# PinscapePico_KL25Z_Adapter_-_74HC165_vsn.net
KiCad netlist of a schematic drawn in EAGLE
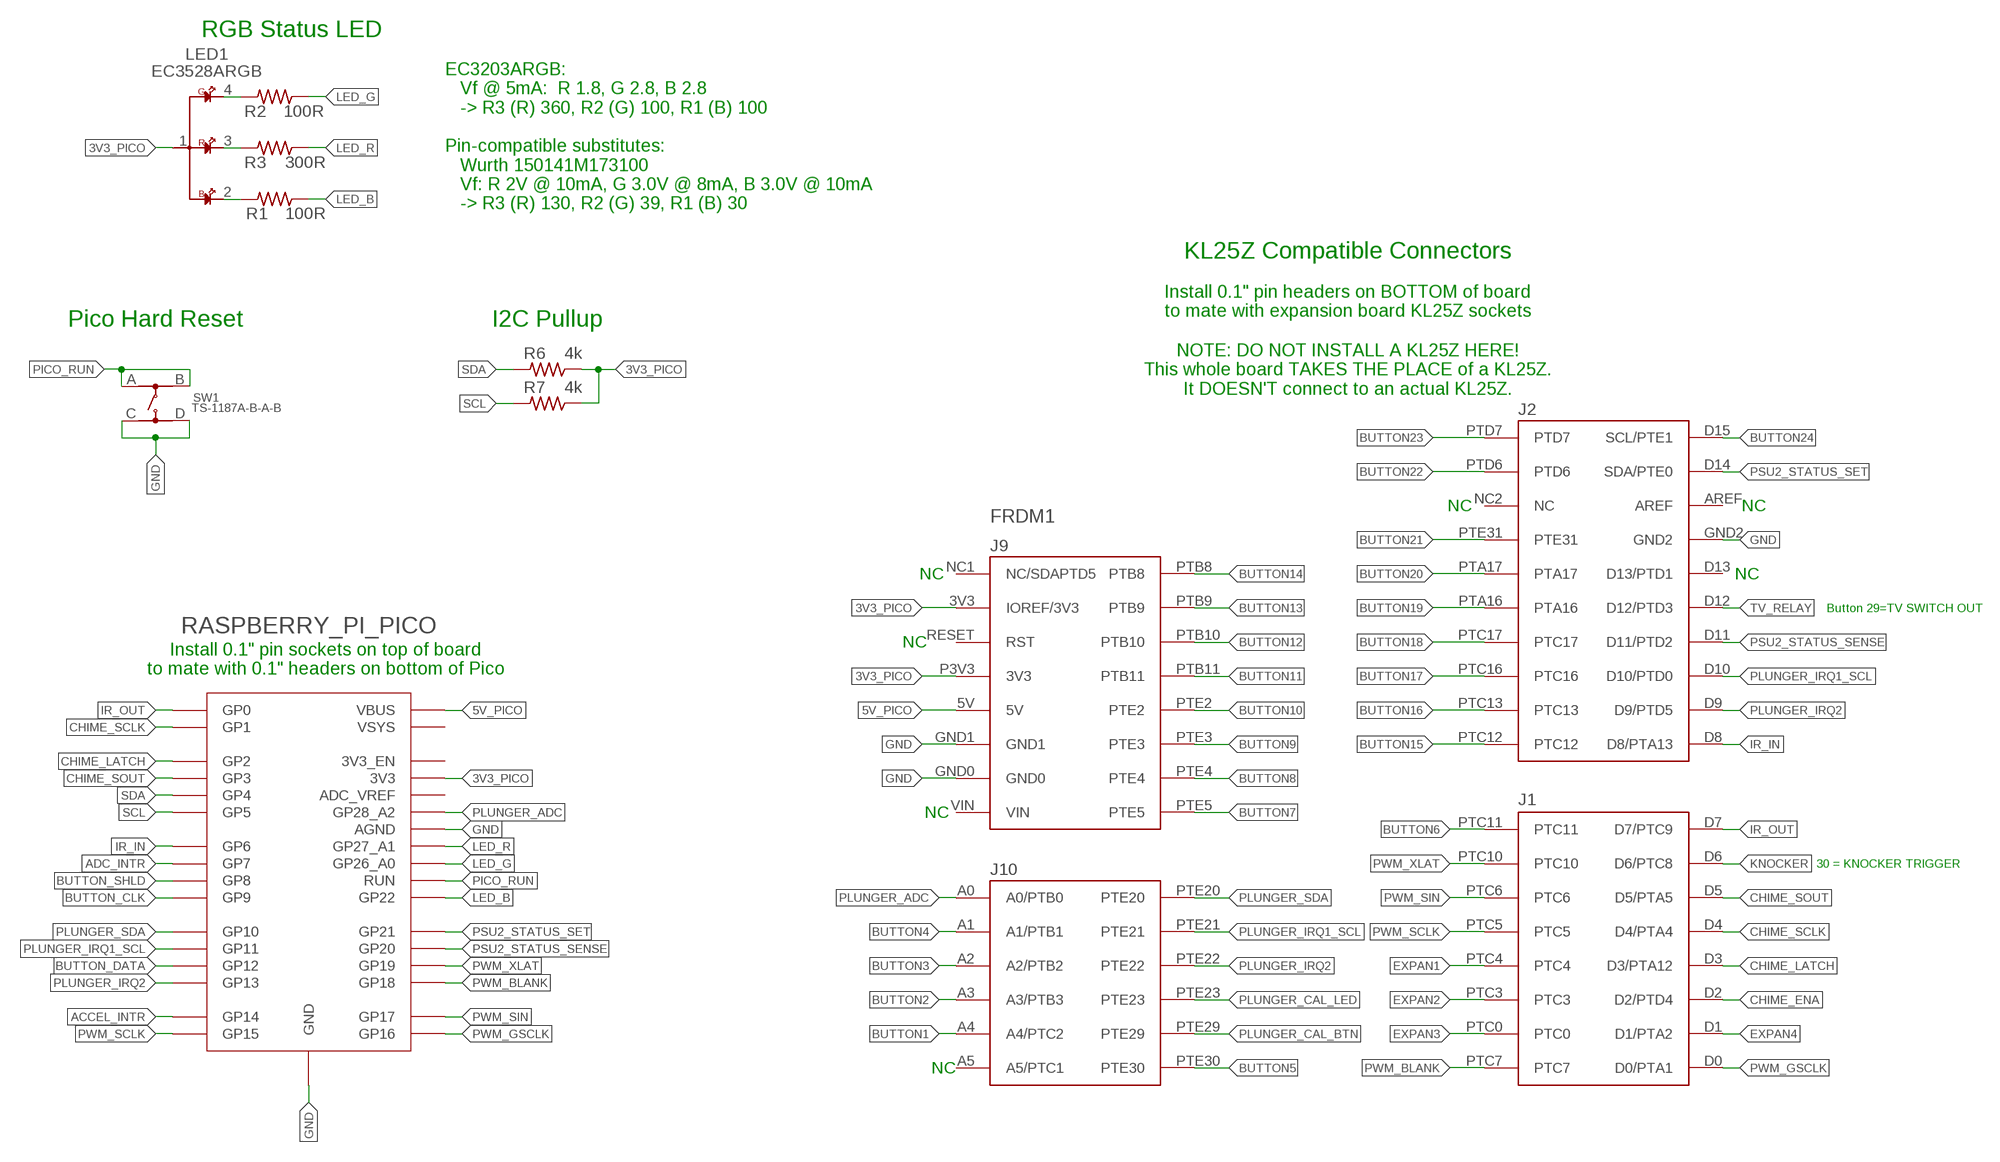
[diagram p0: schematic, sheet 1]
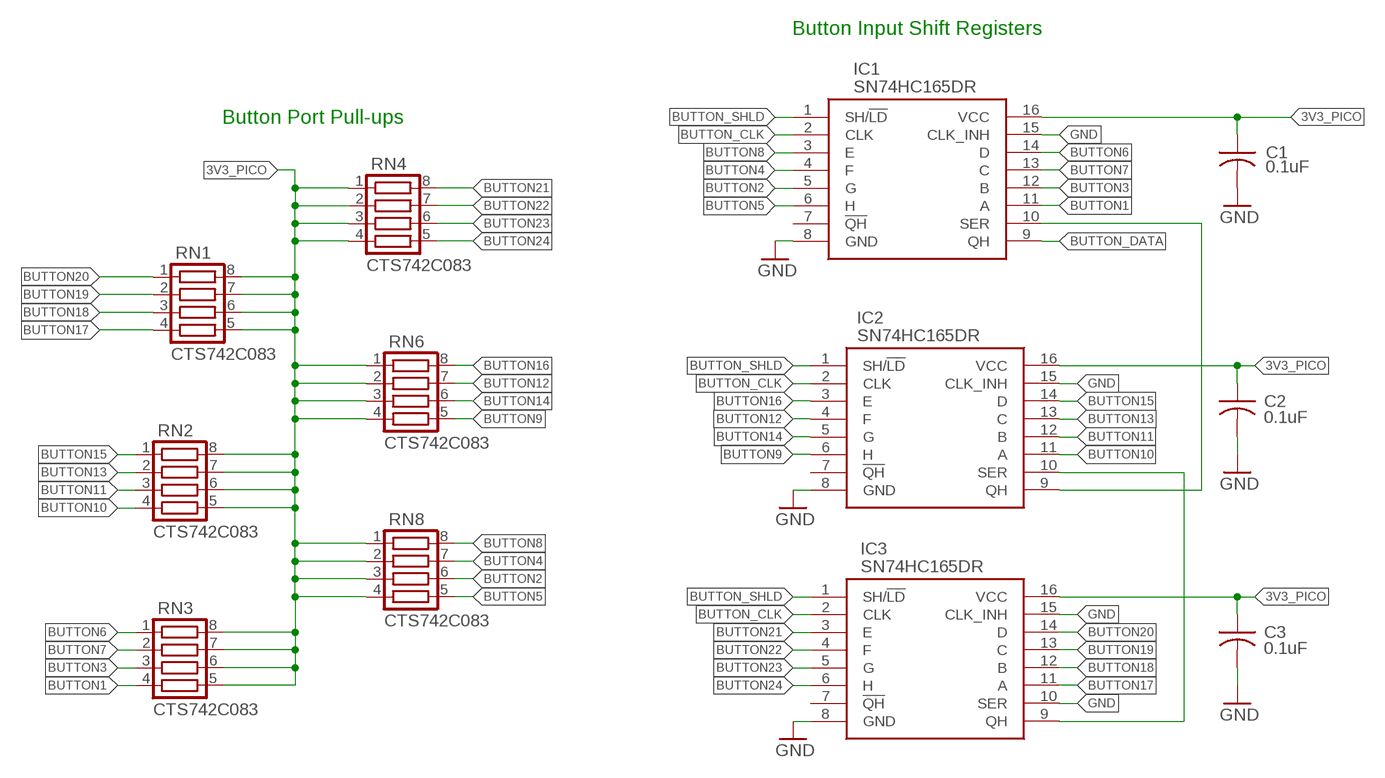
[diagram p1: schematic, sheet 2]
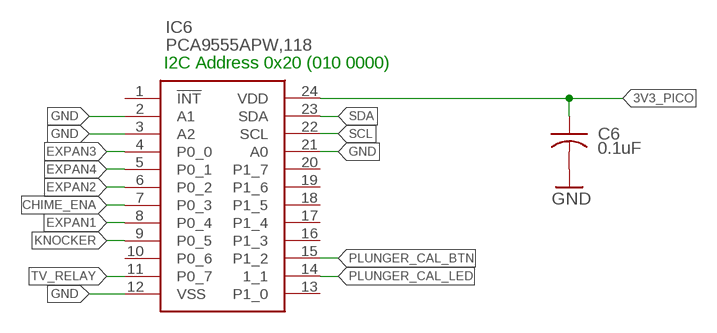
[diagram p2: schematic, sheet 3]
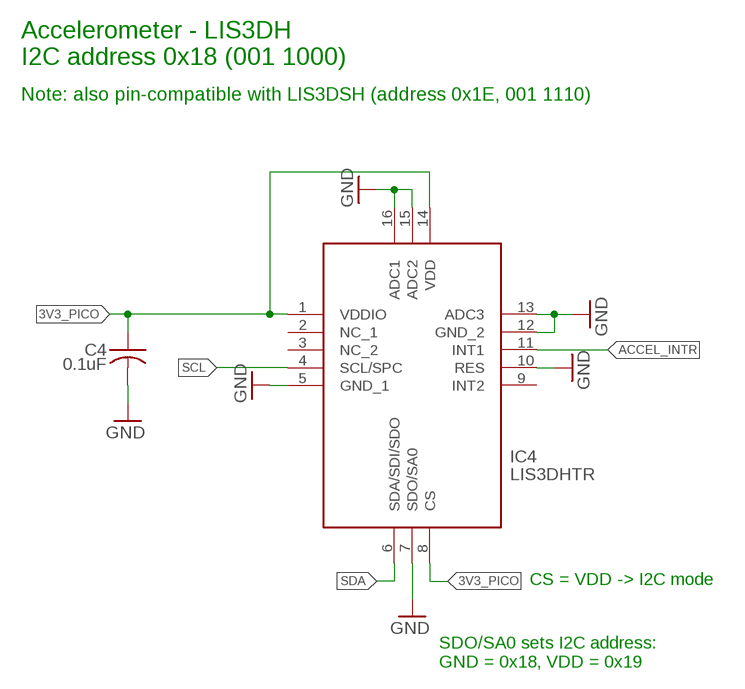
[diagram p3: schematic, sheet 4]
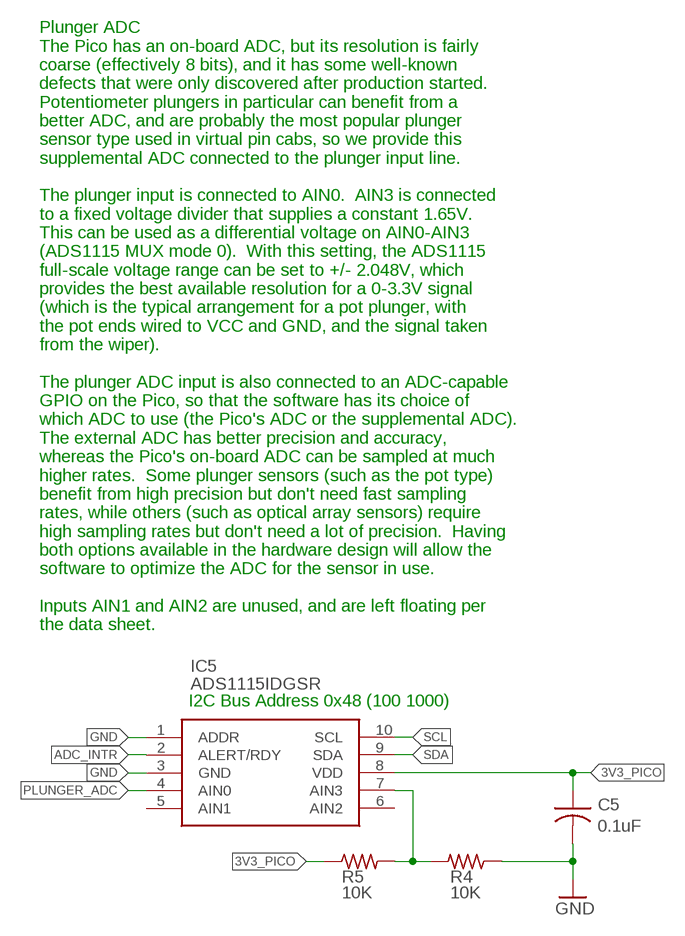
[diagram p4: schematic, sheet 5]
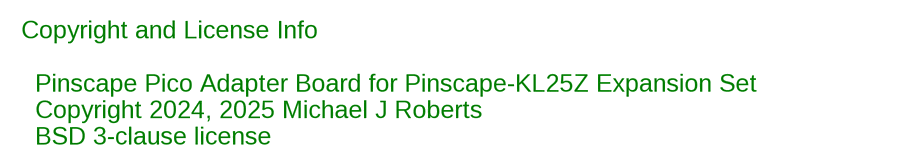
[diagram p5: schematic, sheet 6]

(export (version "E")
  (design (tool "Eeschema 10.0.6"))
  (components
    (comp (ref "FRDM1")
      (value "KL25Z")
      (footprint "eagle-import:FRDM_KL25Z_NORMAL")
      (libsource (lib "eagle-import") (part "FRDM-KL25ZNORMAL"))
    )
    (comp (ref "LED1")
      (value "EC3528ARGB")
      (footprint "eagle-import:EC3528ARGB")
      (libsource (lib "eagle-import") (part "EC3528ARGB"))
    )
    (comp (ref "R1")
      (value "100R")
      (footprint "eagle-import:R1206")
      (libsource (lib "eagle-import") (part "R-US_R1206"))
    )
    (comp (ref "R2")
      (value "100R")
      (footprint "eagle-import:R1206")
      (libsource (lib "eagle-import") (part "R-US_R1206"))
    )
    (comp (ref "R3")
      (value "300R")
      (footprint "eagle-import:R1206")
      (libsource (lib "eagle-import") (part "R-US_R1206"))
    )
    (comp (ref "R6")
      (value "4k")
      (footprint "eagle-import:R1206")
      (libsource (lib "eagle-import") (part "R-US_R1206"))
    )
    (comp (ref "R7")
      (value "4k")
      (footprint "eagle-import:R1206")
      (libsource (lib "eagle-import") (part "R-US_R1206"))
    )
    (comp (ref "RASPBERRY_PI_PICO")
      (value "RPI_PICO_NO_DEBUG")
      (footprint "eagle-import:RPI_PICO_TH_NO_DEBUG")
      (libsource (lib "eagle-import") (part "RPI_PICO_NO_DEBUG"))
    )
    (comp (ref "SW1")
      (value "TS-1187A-B-A-B")
      (footprint "eagle-import:TS-1187A-B-A-B")
      (libsource (lib "eagle-import") (part "TS-1187A-B-A-B"))
    )
    (comp (ref "C5")
      (value "0.1uF")
      (footprint "eagle-import:C1206")
      (libsource (lib "eagle-import") (part "C-USC1206"))
    )
    (comp (ref "IC5")
      (value "ADS1115IDGSR")
      (footprint "eagle-import:SOP50P490X110-10N")
      (fields (field (name "MOUSER_PART_NUMBER") "595-ADS1115IDGSR"))
      (libsource (lib "eagle-import") (part "ADS1115IDGSR"))
    )
    (comp (ref "R4")
      (value "10K")
      (footprint "eagle-import:R1206")
      (libsource (lib "eagle-import") (part "R-US_R1206"))
    )
    (comp (ref "R5")
      (value "10K")
      (footprint "eagle-import:R1206")
      (libsource (lib "eagle-import") (part "R-US_R1206"))
    )
    (comp (ref "C1")
      (value "0.1uF")
      (footprint "eagle-import:C1206")
      (libsource (lib "eagle-import") (part "C-USC1206"))
    )
    (comp (ref "C2")
      (value "0.1uF")
      (footprint "eagle-import:C1206")
      (libsource (lib "eagle-import") (part "C-USC1206"))
    )
    (comp (ref "C3")
      (value "0.1uF")
      (footprint "eagle-import:C1206")
      (libsource (lib "eagle-import") (part "C-USC1206"))
    )
    (comp (ref "IC1")
      (value "SN74HC165DR")
      (footprint "eagle-import:SOIC127P600X175-16N")
      (fields (field (name "MOUSER_PART_NUMBER") "595-SN74HC165DR"))
      (libsource (lib "eagle-import") (part "SN74HC165DR"))
    )
    (comp (ref "IC2")
      (value "SN74HC165DR")
      (footprint "eagle-import:SOIC127P600X175-16N")
      (fields (field (name "MOUSER_PART_NUMBER") "595-SN74HC165DR"))
      (libsource (lib "eagle-import") (part "SN74HC165DR"))
    )
    (comp (ref "IC3")
      (value "SN74HC165DR")
      (footprint "eagle-import:SOIC127P600X175-16N")
      (fields (field (name "MOUSER_PART_NUMBER") "595-SN74HC165DR"))
      (libsource (lib "eagle-import") (part "SN74HC165DR"))
    )
    (comp (ref "RN1")
      (value "CTS742C083")
      (footprint "eagle-import:CTS742C083")
      (libsource (lib "eagle-import") (part "CTS742C083"))
    )
    (comp (ref "RN2")
      (value "CTS742C083")
      (footprint "eagle-import:CTS742C083")
      (libsource (lib "eagle-import") (part "CTS742C083"))
    )
    (comp (ref "RN3")
      (value "CTS742C083")
      (footprint "eagle-import:CTS742C083")
      (libsource (lib "eagle-import") (part "CTS742C083"))
    )
    (comp (ref "RN4")
      (value "CTS742C083")
      (footprint "eagle-import:CTS742C083")
      (libsource (lib "eagle-import") (part "CTS742C083"))
    )
    (comp (ref "RN6")
      (value "CTS742C083")
      (footprint "eagle-import:CTS742C083")
      (libsource (lib "eagle-import") (part "CTS742C083"))
    )
    (comp (ref "RN8")
      (value "CTS742C083")
      (footprint "eagle-import:CTS742C083")
      (libsource (lib "eagle-import") (part "CTS742C083"))
    )
    (comp (ref "C6")
      (value "0.1uF")
      (footprint "eagle-import:C1206")
      (libsource (lib "eagle-import") (part "C-USC1206"))
    )
    (comp (ref "IC6")
      (value "PCA9555APW,118")
      (footprint "eagle-import:SOP65P640X110-24N")
      (fields (field (name "MOUSER_PART_NUMBER") "771-PCA9555APW118"))
      (libsource (lib "eagle-import") (part "PCA9555APW,118"))
    )
    (comp (ref "C4")
      (value "0.1uF")
      (footprint "eagle-import:C1206")
      (libsource (lib "eagle-import") (part "C-USC1206"))
    )
    (comp (ref "IC4")
      (value "LIS3DHTR")
      (footprint "eagle-import:LIS3DHTR")
      (fields (field (name "MOUSER_PART_NUMBER") "511-LIS3DHTR"))
      (libsource (lib "eagle-import") (part "LIS3DHTR"))
    )
  )
  (nets
    (net (code "1") (name "3V3_PICO") (class "Default")
      (node (ref "C1") (pin "1") (pinfunction "1_1") (pintype "passive"))
      (node (ref "C2") (pin "1") (pinfunction "1_1") (pintype "passive"))
      (node (ref "C3") (pin "1") (pinfunction "1_1") (pintype "passive"))
      (node (ref "C4") (pin "1") (pinfunction "1_1") (pintype "passive"))
      (node (ref "C5") (pin "1") (pinfunction "1_1") (pintype "passive"))
      (node (ref "C6") (pin "1") (pinfunction "1_1") (pintype "passive"))
      (node (ref "FRDM1") (pin "3V3") (pinfunction "IOREF/3V3_3V3") (pintype "bidirectional"))
      (node (ref "FRDM1") (pin "P3V3") (pinfunction "3V3_P3V3") (pintype "bidirectional"))
      (node (ref "IC1") (pin "16") (pinfunction "VCC_16") (pintype "bidirectional"))
      (node (ref "IC2") (pin "16") (pinfunction "VCC_16") (pintype "bidirectional"))
      (node (ref "IC3") (pin "16") (pinfunction "VCC_16") (pintype "bidirectional"))
      (node (ref "IC4") (pin "1") (pinfunction "VDDIO_1") (pintype "power_in"))
      (node (ref "IC4") (pin "14") (pinfunction "VDD_14") (pintype "power_in"))
      (node (ref "IC4") (pin "8") (pinfunction "CS_8") (pintype "input"))
      (node (ref "IC5") (pin "8") (pinfunction "VDD_8") (pintype "bidirectional"))
      (node (ref "IC6") (pin "24") (pinfunction "VDD_24") (pintype "bidirectional"))
      (node (ref "LED1") (pin "1") (pinfunction "1_1") (pintype "bidirectional"))
      (node (ref "R5") (pin "1") (pinfunction "1_1") (pintype "passive"))
      (node (ref "R6") (pin "1") (pinfunction "1_1") (pintype "passive"))
      (node (ref "R7") (pin "1") (pinfunction "1_1") (pintype "passive"))
      (node (ref "RASPBERRY_PI_PICO") (pin "3V3") (pinfunction "3V3_3V3") (pintype "bidirectional"))
      (node (ref "RN1") (pin "5") (pinfunction "5_5") (pintype "passive"))
      (node (ref "RN1") (pin "6") (pinfunction "6_6") (pintype "passive"))
      (node (ref "RN1") (pin "7") (pinfunction "7_7") (pintype "passive"))
      (node (ref "RN1") (pin "8") (pinfunction "8_8") (pintype "passive"))
      (node (ref "RN2") (pin "5") (pinfunction "5_5") (pintype "passive"))
      (node (ref "RN2") (pin "6") (pinfunction "6_6") (pintype "passive"))
      (node (ref "RN2") (pin "7") (pinfunction "7_7") (pintype "passive"))
      (node (ref "RN2") (pin "8") (pinfunction "8_8") (pintype "passive"))
      (node (ref "RN3") (pin "5") (pinfunction "5_5") (pintype "passive"))
      (node (ref "RN3") (pin "6") (pinfunction "6_6") (pintype "passive"))
      (node (ref "RN3") (pin "7") (pinfunction "7_7") (pintype "passive"))
      (node (ref "RN3") (pin "8") (pinfunction "8_8") (pintype "passive"))
      (node (ref "RN4") (pin "1") (pinfunction "1_1") (pintype "passive"))
      (node (ref "RN4") (pin "2") (pinfunction "2_2") (pintype "passive"))
      (node (ref "RN4") (pin "3") (pinfunction "3_3") (pintype "passive"))
      (node (ref "RN4") (pin "4") (pinfunction "4_4") (pintype "passive"))
      (node (ref "RN6") (pin "1") (pinfunction "1_1") (pintype "passive"))
      (node (ref "RN6") (pin "2") (pinfunction "2_2") (pintype "passive"))
      (node (ref "RN6") (pin "3") (pinfunction "3_3") (pintype "passive"))
      (node (ref "RN6") (pin "4") (pinfunction "4_4") (pintype "passive"))
      (node (ref "RN8") (pin "1") (pinfunction "1_1") (pintype "passive"))
      (node (ref "RN8") (pin "2") (pinfunction "2_2") (pintype "passive"))
      (node (ref "RN8") (pin "3") (pinfunction "3_3") (pintype "passive"))
      (node (ref "RN8") (pin "4") (pinfunction "4_4") (pintype "passive"))
    )
    (net (code "2") (name "5V_PICO") (class "Default")
      (node (ref "FRDM1") (pin "5V") (pinfunction "5V_5V") (pintype "bidirectional"))
      (node (ref "RASPBERRY_PI_PICO") (pin "VBUS") (pinfunction "VBUS_VBUS") (pintype "bidirectional"))
    )
    (net (code "3") (name "ACCEL_INTR") (class "Default")
      (node (ref "IC4") (pin "11") (pinfunction "INT1_11") (pintype "input"))
      (node (ref "RASPBERRY_PI_PICO") (pin "GP14") (pinfunction "GP14_GP14") (pintype "bidirectional"))
    )
    (net (code "4") (name "ADC_INTR") (class "Default")
      (node (ref "IC5") (pin "2") (pinfunction "ALERT/RDY_2") (pintype "bidirectional"))
      (node (ref "RASPBERRY_PI_PICO") (pin "GP7") (pinfunction "GP7_GP7") (pintype "bidirectional"))
    )
    (net (code "5") (name "BUTTON1") (class "Default")
      (node (ref "FRDM1") (pin "A4") (pinfunction "A4/PTC2_A4") (pintype "bidirectional"))
      (node (ref "IC1") (pin "11") (pinfunction "A_11") (pintype "bidirectional"))
      (node (ref "RN3") (pin "4") (pinfunction "4_4") (pintype "passive"))
    )
    (net (code "6") (name "BUTTON2") (class "Default")
      (node (ref "FRDM1") (pin "A3") (pinfunction "A3/PTB3_A3") (pintype "bidirectional"))
      (node (ref "IC1") (pin "5") (pinfunction "G_5") (pintype "bidirectional"))
      (node (ref "RN8") (pin "6") (pinfunction "6_6") (pintype "passive"))
    )
    (net (code "7") (name "BUTTON3") (class "Default")
      (node (ref "FRDM1") (pin "A2") (pinfunction "A2/PTB2_A2") (pintype "bidirectional"))
      (node (ref "IC1") (pin "12") (pinfunction "B_12") (pintype "bidirectional"))
      (node (ref "RN3") (pin "3") (pinfunction "3_3") (pintype "passive"))
    )
    (net (code "8") (name "BUTTON4") (class "Default")
      (node (ref "FRDM1") (pin "A1") (pinfunction "A1/PTB1_A1") (pintype "bidirectional"))
      (node (ref "IC1") (pin "4") (pinfunction "F_4") (pintype "bidirectional"))
      (node (ref "RN8") (pin "7") (pinfunction "7_7") (pintype "passive"))
    )
    (net (code "9") (name "BUTTON5") (class "Default")
      (node (ref "FRDM1") (pin "PTE30") (pinfunction "PTE30_PTE30") (pintype "bidirectional"))
      (node (ref "IC1") (pin "6") (pinfunction "H_6") (pintype "bidirectional"))
      (node (ref "RN8") (pin "5") (pinfunction "5_5") (pintype "passive"))
    )
    (net (code "10") (name "BUTTON6") (class "Default")
      (node (ref "FRDM1") (pin "PTC11") (pinfunction "PTC11_PTC11") (pintype "bidirectional"))
      (node (ref "IC1") (pin "14") (pinfunction "D_14") (pintype "bidirectional"))
      (node (ref "RN3") (pin "1") (pinfunction "1_1") (pintype "passive"))
    )
    (net (code "11") (name "BUTTON7") (class "Default")
      (node (ref "FRDM1") (pin "PTE5") (pinfunction "PTE5_PTE5") (pintype "bidirectional"))
      (node (ref "IC1") (pin "13") (pinfunction "C_13") (pintype "bidirectional"))
      (node (ref "RN3") (pin "2") (pinfunction "2_2") (pintype "passive"))
    )
    (net (code "12") (name "BUTTON8") (class "Default")
      (node (ref "FRDM1") (pin "PTE4") (pinfunction "PTE4_PTE4") (pintype "bidirectional"))
      (node (ref "IC1") (pin "3") (pinfunction "E_3") (pintype "bidirectional"))
      (node (ref "RN8") (pin "8") (pinfunction "8_8") (pintype "passive"))
    )
    (net (code "13") (name "BUTTON9") (class "Default")
      (node (ref "FRDM1") (pin "PTE3") (pinfunction "PTE3_PTE3") (pintype "bidirectional"))
      (node (ref "IC2") (pin "6") (pinfunction "H_6") (pintype "bidirectional"))
      (node (ref "RN6") (pin "5") (pinfunction "5_5") (pintype "passive"))
    )
    (net (code "14") (name "BUTTON10") (class "Default")
      (node (ref "FRDM1") (pin "PTE2") (pinfunction "PTE2_PTE2") (pintype "bidirectional"))
      (node (ref "IC2") (pin "11") (pinfunction "A_11") (pintype "bidirectional"))
      (node (ref "RN2") (pin "4") (pinfunction "4_4") (pintype "passive"))
    )
    (net (code "15") (name "BUTTON11") (class "Default")
      (node (ref "FRDM1") (pin "PTB11") (pinfunction "PTB11_PTB11") (pintype "bidirectional"))
      (node (ref "IC2") (pin "12") (pinfunction "B_12") (pintype "bidirectional"))
      (node (ref "RN2") (pin "3") (pinfunction "3_3") (pintype "passive"))
    )
    (net (code "16") (name "BUTTON12") (class "Default")
      (node (ref "FRDM1") (pin "PTB10") (pinfunction "PTB10_PTB10") (pintype "bidirectional"))
      (node (ref "IC2") (pin "4") (pinfunction "F_4") (pintype "bidirectional"))
      (node (ref "RN6") (pin "7") (pinfunction "7_7") (pintype "passive"))
    )
    (net (code "17") (name "BUTTON13") (class "Default")
      (node (ref "FRDM1") (pin "PTB9") (pinfunction "PTB9_PTB9") (pintype "bidirectional"))
      (node (ref "IC2") (pin "13") (pinfunction "C_13") (pintype "bidirectional"))
      (node (ref "RN2") (pin "2") (pinfunction "2_2") (pintype "passive"))
    )
    (net (code "18") (name "BUTTON14") (class "Default")
      (node (ref "FRDM1") (pin "PTB8") (pinfunction "PTB8_PTB8") (pintype "bidirectional"))
      (node (ref "IC2") (pin "5") (pinfunction "G_5") (pintype "bidirectional"))
      (node (ref "RN6") (pin "6") (pinfunction "6_6") (pintype "passive"))
    )
    (net (code "19") (name "BUTTON15") (class "Default")
      (node (ref "FRDM1") (pin "PTC12") (pinfunction "PTC12_PTC12") (pintype "bidirectional"))
      (node (ref "IC2") (pin "14") (pinfunction "D_14") (pintype "bidirectional"))
      (node (ref "RN2") (pin "1") (pinfunction "1_1") (pintype "passive"))
    )
    (net (code "20") (name "BUTTON16") (class "Default")
      (node (ref "FRDM1") (pin "PTC13") (pinfunction "PTC13_PTC13") (pintype "bidirectional"))
      (node (ref "IC2") (pin "3") (pinfunction "E_3") (pintype "bidirectional"))
      (node (ref "RN6") (pin "8") (pinfunction "8_8") (pintype "passive"))
    )
    (net (code "21") (name "BUTTON17") (class "Default")
      (node (ref "FRDM1") (pin "PTC16") (pinfunction "PTC16_PTC16") (pintype "bidirectional"))
      (node (ref "IC3") (pin "11") (pinfunction "A_11") (pintype "bidirectional"))
      (node (ref "RN1") (pin "4") (pinfunction "4_4") (pintype "passive"))
    )
    (net (code "22") (name "BUTTON18") (class "Default")
      (node (ref "FRDM1") (pin "PTC17") (pinfunction "PTC17_PTC17") (pintype "bidirectional"))
      (node (ref "IC3") (pin "12") (pinfunction "B_12") (pintype "bidirectional"))
      (node (ref "RN1") (pin "3") (pinfunction "3_3") (pintype "passive"))
    )
    (net (code "23") (name "BUTTON19") (class "Default")
      (node (ref "FRDM1") (pin "PTA16") (pinfunction "PTA16_PTA16") (pintype "bidirectional"))
      (node (ref "IC3") (pin "13") (pinfunction "C_13") (pintype "bidirectional"))
      (node (ref "RN1") (pin "2") (pinfunction "2_2") (pintype "passive"))
    )
    (net (code "24") (name "BUTTON20") (class "Default")
      (node (ref "FRDM1") (pin "PTA17") (pinfunction "PTA17_PTA17") (pintype "bidirectional"))
      (node (ref "IC3") (pin "14") (pinfunction "D_14") (pintype "bidirectional"))
      (node (ref "RN1") (pin "1") (pinfunction "1_1") (pintype "passive"))
    )
    (net (code "25") (name "BUTTON21") (class "Default")
      (node (ref "FRDM1") (pin "PTE31") (pinfunction "PTE31_PTE31") (pintype "bidirectional"))
      (node (ref "IC3") (pin "3") (pinfunction "E_3") (pintype "bidirectional"))
      (node (ref "RN4") (pin "8") (pinfunction "8_8") (pintype "passive"))
    )
    (net (code "26") (name "BUTTON22") (class "Default")
      (node (ref "FRDM1") (pin "PTD6") (pinfunction "PTD6_PTD6") (pintype "bidirectional"))
      (node (ref "IC3") (pin "4") (pinfunction "F_4") (pintype "bidirectional"))
      (node (ref "RN4") (pin "7") (pinfunction "7_7") (pintype "passive"))
    )
    (net (code "27") (name "BUTTON23") (class "Default")
      (node (ref "FRDM1") (pin "PTD7") (pinfunction "PTD7_PTD7") (pintype "bidirectional"))
      (node (ref "IC3") (pin "5") (pinfunction "G_5") (pintype "bidirectional"))
      (node (ref "RN4") (pin "6") (pinfunction "6_6") (pintype "passive"))
    )
    (net (code "28") (name "BUTTON24") (class "Default")
      (node (ref "FRDM1") (pin "D15") (pinfunction "SCL/PTE1_D15") (pintype "bidirectional"))
      (node (ref "IC3") (pin "6") (pinfunction "H_6") (pintype "bidirectional"))
      (node (ref "RN4") (pin "5") (pinfunction "5_5") (pintype "passive"))
    )
    (net (code "29") (name "BUTTON_CLK") (class "Default")
      (node (ref "IC1") (pin "2") (pinfunction "CLK_2") (pintype "bidirectional"))
      (node (ref "IC2") (pin "2") (pinfunction "CLK_2") (pintype "bidirectional"))
      (node (ref "IC3") (pin "2") (pinfunction "CLK_2") (pintype "bidirectional"))
      (node (ref "RASPBERRY_PI_PICO") (pin "GP9") (pinfunction "GP9_GP9") (pintype "bidirectional"))
    )
    (net (code "30") (name "BUTTON_DATA") (class "Default")
      (node (ref "IC1") (pin "9") (pinfunction "QH_9") (pintype "bidirectional"))
      (node (ref "RASPBERRY_PI_PICO") (pin "GP12") (pinfunction "GP12_GP12") (pintype "bidirectional"))
    )
    (net (code "31") (name "BUTTON_SHLD") (class "Default")
      (node (ref "IC1") (pin "1") (pinfunction "SH/~{LD}_1") (pintype "bidirectional"))
      (node (ref "IC2") (pin "1") (pinfunction "SH/~{LD}_1") (pintype "bidirectional"))
      (node (ref "IC3") (pin "1") (pinfunction "SH/~{LD}_1") (pintype "bidirectional"))
      (node (ref "RASPBERRY_PI_PICO") (pin "GP8") (pinfunction "GP8_GP8") (pintype "bidirectional"))
    )
    (net (code "32") (name "CHIME_ENA") (class "Default")
      (node (ref "FRDM1") (pin "D2") (pinfunction "D2/PTD4_D2") (pintype "bidirectional"))
      (node (ref "IC6") (pin "7") (pinfunction "P0_3_7") (pintype "bidirectional"))
    )
    (net (code "33") (name "CHIME_LATCH") (class "Default")
      (node (ref "FRDM1") (pin "D3") (pinfunction "D3/PTA12_D3") (pintype "bidirectional"))
      (node (ref "RASPBERRY_PI_PICO") (pin "GP2") (pinfunction "GP2_GP2") (pintype "bidirectional"))
    )
    (net (code "34") (name "CHIME_SCLK") (class "Default")
      (node (ref "FRDM1") (pin "D4") (pinfunction "D4/PTA4_D4") (pintype "bidirectional"))
      (node (ref "RASPBERRY_PI_PICO") (pin "GP1") (pinfunction "GP1_GP1") (pintype "bidirectional"))
    )
    (net (code "35") (name "CHIME_SOUT") (class "Default")
      (node (ref "FRDM1") (pin "D5") (pinfunction "D5/PTA5_D5") (pintype "bidirectional"))
      (node (ref "RASPBERRY_PI_PICO") (pin "GP3") (pinfunction "GP3_GP3") (pintype "bidirectional"))
    )
    (net (code "36") (name "EXPAN1") (class "Default")
      (node (ref "FRDM1") (pin "PTC4") (pinfunction "PTC4_PTC4") (pintype "bidirectional"))
      (node (ref "IC6") (pin "8") (pinfunction "P0_4_8") (pintype "bidirectional"))
    )
    (net (code "37") (name "EXPAN2") (class "Default")
      (node (ref "FRDM1") (pin "PTC3") (pinfunction "PTC3_PTC3") (pintype "bidirectional"))
      (node (ref "IC6") (pin "6") (pinfunction "P0_2_6") (pintype "bidirectional"))
    )
    (net (code "38") (name "EXPAN3") (class "Default")
      (node (ref "FRDM1") (pin "PTC0") (pinfunction "PTC0_PTC0") (pintype "bidirectional"))
      (node (ref "IC6") (pin "4") (pinfunction "P0_0_4") (pintype "bidirectional"))
    )
    (net (code "39") (name "EXPAN4") (class "Default")
      (node (ref "FRDM1") (pin "D1") (pinfunction "D1/PTA2_D1") (pintype "bidirectional"))
      (node (ref "IC6") (pin "5") (pinfunction "P0_1_5") (pintype "bidirectional"))
    )
    (net (code "40") (name "GND") (class "Default")
      (node (ref "C1") (pin "2") (pinfunction "2_2") (pintype "passive"))
      (node (ref "C2") (pin "2") (pinfunction "2_2") (pintype "passive"))
      (node (ref "C3") (pin "2") (pinfunction "2_2") (pintype "passive"))
      (node (ref "C4") (pin "2") (pinfunction "2_2") (pintype "passive"))
      (node (ref "C5") (pin "2") (pinfunction "2_2") (pintype "passive"))
      (node (ref "C6") (pin "2") (pinfunction "2_2") (pintype "passive"))
      (node (ref "FRDM1") (pin "GND0") (pinfunction "GND0_GND0") (pintype "bidirectional"))
      (node (ref "FRDM1") (pin "GND1") (pinfunction "GND1_GND1") (pintype "bidirectional"))
      (node (ref "FRDM1") (pin "GND2") (pinfunction "GND2_GND2") (pintype "bidirectional"))
      (node (ref "IC1") (pin "15") (pinfunction "CLK_INH_15") (pintype "bidirectional"))
      (node (ref "IC1") (pin "8") (pinfunction "GND_8") (pintype "bidirectional"))
      (node (ref "IC2") (pin "15") (pinfunction "CLK_INH_15") (pintype "bidirectional"))
      (node (ref "IC2") (pin "8") (pinfunction "GND_8") (pintype "bidirectional"))
      (node (ref "IC3") (pin "10") (pinfunction "SER_10") (pintype "bidirectional"))
      (node (ref "IC3") (pin "15") (pinfunction "CLK_INH_15") (pintype "bidirectional"))
      (node (ref "IC3") (pin "8") (pinfunction "GND_8") (pintype "bidirectional"))
      (node (ref "IC4") (pin "10") (pinfunction "RES_10") (pintype "bidirectional"))
      (node (ref "IC4") (pin "12") (pinfunction "GND_2_12") (pintype "power_in"))
      (node (ref "IC4") (pin "13") (pinfunction "ADC3_13") (pintype "bidirectional"))
      (node (ref "IC4") (pin "15") (pinfunction "ADC2_15") (pintype "bidirectional"))
      (node (ref "IC4") (pin "16") (pinfunction "ADC1_16") (pintype "bidirectional"))
      (node (ref "IC4") (pin "5") (pinfunction "GND_1_5") (pintype "power_in"))
      (node (ref "IC4") (pin "7") (pinfunction "SDO/SA0_7") (pintype "bidirectional"))
      (node (ref "IC5") (pin "1") (pinfunction "ADDR_1") (pintype "bidirectional"))
      (node (ref "IC5") (pin "3") (pinfunction "GND_3") (pintype "bidirectional"))
      (node (ref "IC6") (pin "12") (pinfunction "VSS_12") (pintype "bidirectional"))
      (node (ref "IC6") (pin "2") (pinfunction "A1_2") (pintype "bidirectional"))
      (node (ref "IC6") (pin "21") (pinfunction "A0_21") (pintype "bidirectional"))
      (node (ref "IC6") (pin "3") (pinfunction "A2_3") (pintype "bidirectional"))
      (node (ref "R4") (pin "1") (pinfunction "1_1") (pintype "passive"))
      (node (ref "RASPBERRY_PI_PICO") (pin "AGND") (pinfunction "AGND_AGND") (pintype "bidirectional"))
      (node (ref "RASPBERRY_PI_PICO") (pin "GND@1") (pinfunction "GND_GND@1") (pintype "bidirectional"))
      (node (ref "RASPBERRY_PI_PICO") (pin "GND@2") (pinfunction "GND_GND@2") (pintype "bidirectional"))
      (node (ref "RASPBERRY_PI_PICO") (pin "GND@3") (pinfunction "GND_GND@3") (pintype "bidirectional"))
      (node (ref "RASPBERRY_PI_PICO") (pin "GND@4") (pinfunction "GND_GND@4") (pintype "bidirectional"))
      (node (ref "RASPBERRY_PI_PICO") (pin "GND@6") (pinfunction "GND_GND@6") (pintype "bidirectional"))
      (node (ref "RASPBERRY_PI_PICO") (pin "GND@7") (pinfunction "GND_GND@7") (pintype "bidirectional"))
      (node (ref "RASPBERRY_PI_PICO") (pin "GND@8") (pinfunction "GND_GND@8") (pintype "bidirectional"))
      (node (ref "SW1") (pin "C") (pinfunction "C_C") (pintype "bidirectional"))
      (node (ref "SW1") (pin "D") (pinfunction "D_D") (pintype "bidirectional"))
    )
    (net (code "41") (name "IR_IN") (class "Default")
      (node (ref "FRDM1") (pin "D8") (pinfunction "D8/PTA13_D8") (pintype "bidirectional"))
      (node (ref "RASPBERRY_PI_PICO") (pin "GP6") (pinfunction "GP6_GP6") (pintype "bidirectional"))
    )
    (net (code "42") (name "IR_OUT") (class "Default")
      (node (ref "FRDM1") (pin "D7") (pinfunction "D7/PTC9_D7") (pintype "bidirectional"))
      (node (ref "RASPBERRY_PI_PICO") (pin "GP0") (pinfunction "GP0_GP0") (pintype "bidirectional"))
    )
    (net (code "43") (name "KNOCKER") (class "Default")
      (node (ref "FRDM1") (pin "D6") (pinfunction "D6/PTC8_D6") (pintype "bidirectional"))
      (node (ref "IC6") (pin "9") (pinfunction "P0_5_9") (pintype "bidirectional"))
    )
    (net (code "44") (name "LED_B") (class "Default")
      (node (ref "R1") (pin "1") (pinfunction "1_1") (pintype "passive"))
      (node (ref "RASPBERRY_PI_PICO") (pin "GP22") (pinfunction "GP22_GP22") (pintype "bidirectional"))
    )
    (net (code "45") (name "LED_G") (class "Default")
      (node (ref "R2") (pin "1") (pinfunction "1_1") (pintype "passive"))
      (node (ref "RASPBERRY_PI_PICO") (pin "GP26_A0") (pinfunction "GP26_A0_GP26_A0") (pintype "bidirectional"))
    )
    (net (code "46") (name "LED_R") (class "Default")
      (node (ref "R3") (pin "1") (pinfunction "1_1") (pintype "passive"))
      (node (ref "RASPBERRY_PI_PICO") (pin "GP27_A1") (pinfunction "GP27_A1_GP27_A1") (pintype "bidirectional"))
    )
    (net (code "47") (name "Net-(IC1-SER)") (class "Default")
      (node (ref "IC1") (pin "10") (pinfunction "SER_10") (pintype "bidirectional"))
      (node (ref "IC2") (pin "9") (pinfunction "QH_9") (pintype "bidirectional"))
    )
    (net (code "48") (name "Net-(IC2-SER)") (class "Default")
      (node (ref "IC2") (pin "10") (pinfunction "SER_10") (pintype "bidirectional"))
      (node (ref "IC3") (pin "9") (pinfunction "QH_9") (pintype "bidirectional"))
    )
    (net (code "49") (name "Net-(IC5-AIN3)") (class "Default")
      (node (ref "IC5") (pin "7") (pinfunction "AIN3_7") (pintype "bidirectional"))
      (node (ref "R4") (pin "2") (pinfunction "2_2") (pintype "passive"))
      (node (ref "R5") (pin "2") (pinfunction "2_2") (pintype "passive"))
    )
    (net (code "50") (name "Net-(LED1-Pad2)") (class "Default")
      (node (ref "LED1") (pin "2") (pinfunction "2_2") (pintype "bidirectional"))
      (node (ref "R1") (pin "2") (pinfunction "2_2") (pintype "passive"))
    )
    (net (code "51") (name "Net-(LED1-Pad3)") (class "Default")
      (node (ref "LED1") (pin "3") (pinfunction "3_3") (pintype "bidirectional"))
      (node (ref "R3") (pin "2") (pinfunction "2_2") (pintype "passive"))
    )
    (net (code "52") (name "Net-(LED1-Pad4)") (class "Default")
      (node (ref "LED1") (pin "4") (pinfunction "4_4") (pintype "bidirectional"))
      (node (ref "R2") (pin "2") (pinfunction "2_2") (pintype "passive"))
    )
    (net (code "53") (name "PICO_RUN") (class "Default")
      (node (ref "RASPBERRY_PI_PICO") (pin "RUN") (pinfunction "RUN_RUN") (pintype "bidirectional"))
      (node (ref "SW1") (pin "A") (pinfunction "A_A") (pintype "bidirectional"))
      (node (ref "SW1") (pin "B") (pinfunction "B_B") (pintype "bidirectional"))
    )
    (net (code "54") (name "PLUNGER_ADC") (class "Default")
      (node (ref "FRDM1") (pin "A0") (pinfunction "A0/PTB0_A0") (pintype "bidirectional"))
      (node (ref "IC5") (pin "4") (pinfunction "AIN0_4") (pintype "bidirectional"))
      (node (ref "RASPBERRY_PI_PICO") (pin "GP28_A2") (pinfunction "GP28_A2_GP28_A2") (pintype "bidirectional"))
    )
    (net (code "55") (name "PLUNGER_CAL_BTN") (class "Default")
      (node (ref "FRDM1") (pin "PTE29") (pinfunction "PTE29_PTE29") (pintype "bidirectional"))
      (node (ref "IC6") (pin "15") (pinfunction "P1_2_15") (pintype "bidirectional"))
    )
    (net (code "56") (name "PLUNGER_CAL_LED") (class "Default")
      (node (ref "FRDM1") (pin "PTE23") (pinfunction "PTE23_PTE23") (pintype "bidirectional"))
      (node (ref "IC6") (pin "14") (pinfunction "1_1_14") (pintype "bidirectional"))
    )
    (net (code "57") (name "PLUNGER_IRQ1_SCL") (class "Default")
      (node (ref "FRDM1") (pin "D10") (pinfunction "D10/PTD0_D10") (pintype "bidirectional"))
      (node (ref "FRDM1") (pin "PTE21") (pinfunction "PTE21_PTE21") (pintype "bidirectional"))
      (node (ref "RASPBERRY_PI_PICO") (pin "GP11") (pinfunction "GP11_GP11") (pintype "bidirectional"))
    )
    (net (code "58") (name "PLUNGER_IRQ2") (class "Default")
      (node (ref "FRDM1") (pin "D9") (pinfunction "D9/PTD5_D9") (pintype "bidirectional"))
      (node (ref "FRDM1") (pin "PTE22") (pinfunction "PTE22_PTE22") (pintype "bidirectional"))
      (node (ref "RASPBERRY_PI_PICO") (pin "GP13") (pinfunction "GP13_GP13") (pintype "bidirectional"))
    )
    (net (code "59") (name "PLUNGER_SDA") (class "Default")
      (node (ref "FRDM1") (pin "PTE20") (pinfunction "PTE20_PTE20") (pintype "bidirectional"))
      (node (ref "RASPBERRY_PI_PICO") (pin "GP10") (pinfunction "GP10_GP10") (pintype "bidirectional"))
    )
    (net (code "60") (name "PSU2_STATUS_SENSE") (class "Default")
      (node (ref "FRDM1") (pin "D11") (pinfunction "D11/PTD2_D11") (pintype "bidirectional"))
      (node (ref "RASPBERRY_PI_PICO") (pin "GP20") (pinfunction "GP20_GP20") (pintype "bidirectional"))
    )
    (net (code "61") (name "PSU2_STATUS_SET") (class "Default")
      (node (ref "FRDM1") (pin "D14") (pinfunction "SDA/PTE0_D14") (pintype "bidirectional"))
      (node (ref "RASPBERRY_PI_PICO") (pin "GP21") (pinfunction "GP21_GP21") (pintype "bidirectional"))
    )
    (net (code "62") (name "PWM_BLANK") (class "Default")
      (node (ref "FRDM1") (pin "PTC7") (pinfunction "PTC7_PTC7") (pintype "bidirectional"))
      (node (ref "RASPBERRY_PI_PICO") (pin "GP18") (pinfunction "GP18_GP18") (pintype "bidirectional"))
    )
    (net (code "63") (name "PWM_GSCLK") (class "Default")
      (node (ref "FRDM1") (pin "D0") (pinfunction "D0/PTA1_D0") (pintype "bidirectional"))
      (node (ref "RASPBERRY_PI_PICO") (pin "GP16") (pinfunction "GP16_GP16") (pintype "bidirectional"))
    )
    (net (code "64") (name "PWM_SCLK") (class "Default")
      (node (ref "FRDM1") (pin "PTC5") (pinfunction "PTC5_PTC5") (pintype "bidirectional"))
      (node (ref "RASPBERRY_PI_PICO") (pin "GP15") (pinfunction "GP15_GP15") (pintype "bidirectional"))
    )
    (net (code "65") (name "PWM_SIN") (class "Default")
      (node (ref "FRDM1") (pin "PTC6") (pinfunction "PTC6_PTC6") (pintype "bidirectional"))
      (node (ref "RASPBERRY_PI_PICO") (pin "GP17") (pinfunction "GP17_GP17") (pintype "bidirectional"))
    )
    (net (code "66") (name "PWM_XLAT") (class "Default")
      (node (ref "FRDM1") (pin "PTC10") (pinfunction "PTC10_PTC10") (pintype "bidirectional"))
      (node (ref "RASPBERRY_PI_PICO") (pin "GP19") (pinfunction "GP19_GP19") (pintype "bidirectional"))
    )
    (net (code "67") (name "SCL") (class "Default")
      (node (ref "IC4") (pin "4") (pinfunction "SCL/SPC_4") (pintype "bidirectional"))
      (node (ref "IC5") (pin "10") (pinfunction "SCL_10") (pintype "bidirectional"))
      (node (ref "IC6") (pin "22") (pinfunction "SCL_22") (pintype "bidirectional"))
      (node (ref "R7") (pin "2") (pinfunction "2_2") (pintype "passive"))
      (node (ref "RASPBERRY_PI_PICO") (pin "GP5") (pinfunction "GP5_GP5") (pintype "bidirectional"))
    )
    (net (code "68") (name "SDA") (class "Default")
      (node (ref "IC4") (pin "6") (pinfunction "SDA/SDI/SDO_6") (pintype "bidirectional"))
      (node (ref "IC5") (pin "9") (pinfunction "SDA_9") (pintype "bidirectional"))
      (node (ref "IC6") (pin "23") (pinfunction "SDA_23") (pintype "bidirectional"))
      (node (ref "R6") (pin "2") (pinfunction "2_2") (pintype "passive"))
      (node (ref "RASPBERRY_PI_PICO") (pin "GP4") (pinfunction "GP4_GP4") (pintype "bidirectional"))
    )
    (net (code "69") (name "TV_RELAY") (class "Default")
      (node (ref "FRDM1") (pin "D12") (pinfunction "D12/PTD3_D12") (pintype "bidirectional"))
      (node (ref "IC6") (pin "11") (pinfunction "P0_7_11") (pintype "bidirectional"))
    )
    (net (code "70") (name "unconnected-(FRDM1-A5{slash}PTC1-PadA5)") (class "Default")
      (node (ref "FRDM1") (pin "A5") (pinfunction "A5/PTC1_A5") (pintype "bidirectional"))
    )
    (net (code "71") (name "unconnected-(FRDM1-D13{slash}PTD1-PadD13)") (class "Default")
      (node (ref "FRDM1") (pin "D13") (pinfunction "D13/PTD1_D13") (pintype "bidirectional"))
    )
    (net (code "72") (name "unconnected-(FRDM1-NC-PadNC2)") (class "Default")
      (node (ref "FRDM1") (pin "NC2") (pinfunction "NC_NC2") (pintype "bidirectional"))
    )
    (net (code "73") (name "unconnected-(FRDM1-NC{slash}SDAPTD5-PadNC1)") (class "Default")
      (node (ref "FRDM1") (pin "NC1") (pinfunction "NC/SDAPTD5_NC1") (pintype "bidirectional"))
    )
    (net (code "74") (name "unconnected-(FRDM1-PadAREF)") (class "Default")
      (node (ref "FRDM1") (pin "AREF") (pinfunction "AREF_AREF") (pintype "bidirectional"))
    )
    (net (code "75") (name "unconnected-(FRDM1-PadVIN)") (class "Default")
      (node (ref "FRDM1") (pin "VIN") (pinfunction "VIN_VIN") (pintype "bidirectional"))
    )
    (net (code "76") (name "unconnected-(FRDM1-RST-PadRESET)") (class "Default")
      (node (ref "FRDM1") (pin "RESET") (pinfunction "RST_RESET") (pintype "bidirectional"))
    )
    (net (code "77") (name "unconnected-(IC1-~{QH}-Pad7)") (class "Default")
      (node (ref "IC1") (pin "7") (pinfunction "~{QH}_7") (pintype "bidirectional"))
    )
    (net (code "78") (name "unconnected-(IC2-~{QH}-Pad7)") (class "Default")
      (node (ref "IC2") (pin "7") (pinfunction "~{QH}_7") (pintype "bidirectional"))
    )
    (net (code "79") (name "unconnected-(IC3-~{QH}-Pad7)") (class "Default")
      (node (ref "IC3") (pin "7") (pinfunction "~{QH}_7") (pintype "bidirectional"))
    )
    (net (code "80") (name "unconnected-(IC4-INT2-Pad9)") (class "Default")
      (node (ref "IC4") (pin "9") (pinfunction "INT2_9") (pintype "input"))
    )
    (net (code "81") (name "unconnected-(IC4-NC_1-Pad2)") (class "Default")
      (node (ref "IC4") (pin "2") (pinfunction "NC_1_2") (pintype "bidirectional"))
    )
    (net (code "82") (name "unconnected-(IC4-NC_2-Pad3)") (class "Default")
      (node (ref "IC4") (pin "3") (pinfunction "NC_2_3") (pintype "bidirectional"))
    )
    (net (code "83") (name "unconnected-(IC5-AIN1-Pad5)") (class "Default")
      (node (ref "IC5") (pin "5") (pinfunction "AIN1_5") (pintype "bidirectional"))
    )
    (net (code "84") (name "unconnected-(IC5-AIN2-Pad6)") (class "Default")
      (node (ref "IC5") (pin "6") (pinfunction "AIN2_6") (pintype "bidirectional"))
    )
    (net (code "85") (name "unconnected-(IC6-P0_6-Pad10)") (class "Default")
      (node (ref "IC6") (pin "10") (pinfunction "P0_6_10") (pintype "bidirectional"))
    )
    (net (code "86") (name "unconnected-(IC6-P1_0-Pad13)") (class "Default")
      (node (ref "IC6") (pin "13") (pinfunction "P1_0_13") (pintype "bidirectional"))
    )
    (net (code "87") (name "unconnected-(IC6-P1_3-Pad16)") (class "Default")
      (node (ref "IC6") (pin "16") (pinfunction "P1_3_16") (pintype "bidirectional"))
    )
    (net (code "88") (name "unconnected-(IC6-P1_4-Pad17)") (class "Default")
      (node (ref "IC6") (pin "17") (pinfunction "P1_4_17") (pintype "bidirectional"))
    )
    (net (code "89") (name "unconnected-(IC6-P1_5-Pad18)") (class "Default")
      (node (ref "IC6") (pin "18") (pinfunction "P1_5_18") (pintype "bidirectional"))
    )
    (net (code "90") (name "unconnected-(IC6-P1_6-Pad19)") (class "Default")
      (node (ref "IC6") (pin "19") (pinfunction "P1_6_19") (pintype "bidirectional"))
    )
    (net (code "91") (name "unconnected-(IC6-P1_7-Pad20)") (class "Default")
      (node (ref "IC6") (pin "20") (pinfunction "P1_7_20") (pintype "bidirectional"))
    )
    (net (code "92") (name "unconnected-(IC6-~{INT}-Pad1)") (class "Default")
      (node (ref "IC6") (pin "1") (pinfunction "~{INT}_1") (pintype "bidirectional"))
    )
    (net (code "93") (name "unconnected-(RASPBERRY_PI_PICO-Pad3V3_EN)") (class "Default")
      (node (ref "RASPBERRY_PI_PICO") (pin "3V3_EN") (pinfunction "3V3_EN_3V3_EN") (pintype "bidirectional"))
    )
    (net (code "94") (name "unconnected-(RASPBERRY_PI_PICO-PadADC_VREF)") (class "Default")
      (node (ref "RASPBERRY_PI_PICO") (pin "ADC_VREF") (pinfunction "ADC_VREF_ADC_VREF") (pintype "bidirectional"))
    )
    (net (code "95") (name "unconnected-(RASPBERRY_PI_PICO-PadVSYS)") (class "Default")
      (node (ref "RASPBERRY_PI_PICO") (pin "VSYS") (pinfunction "VSYS_VSYS") (pintype "bidirectional"))
    )
  )
)
